# design.net
KiCad netlist of a schematic drawn in Altium Designer
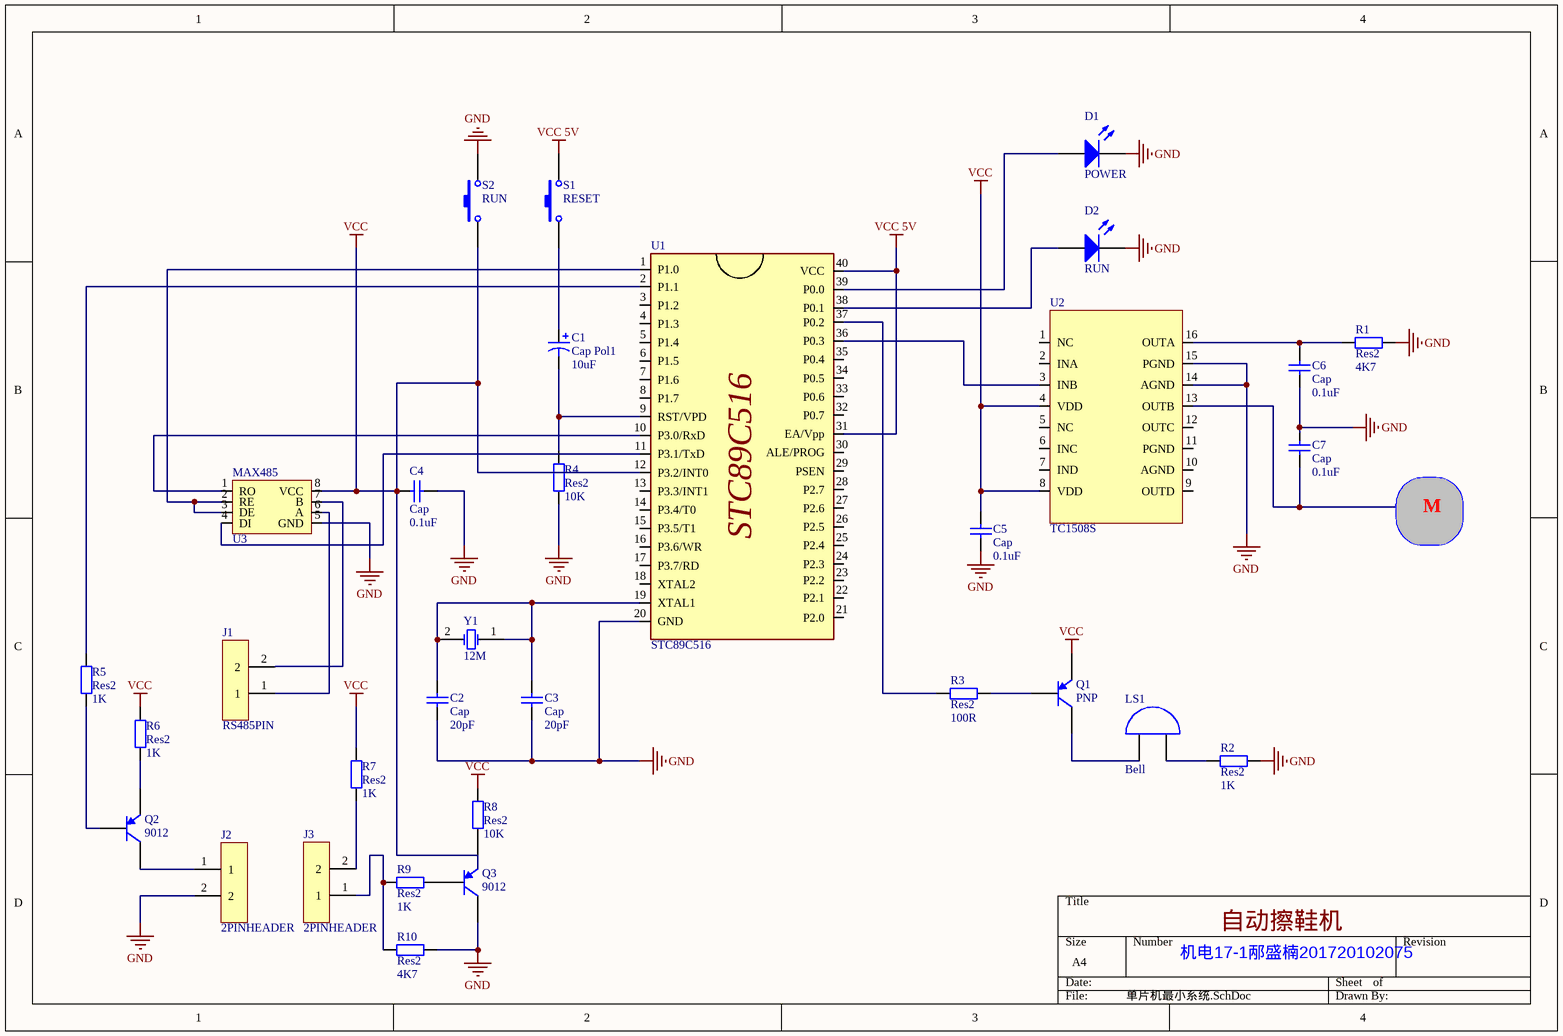
[diagram p0: 单片机最小系统.SchDoc]

(export (version "E")
  (design (tool "Eeschema 10.0.6"))
  (components
    (comp (ref "C1")
      (value "Cap Pol1")
      (footprint "RB7.6-15")
      (description "Polarized Capacitor (Radial)")
      (fields (field (name "ALTIUM_VALUE") "10uF") (field (name "PUBLISHER") "Altium Limited"))
      (libsource (lib "Miscellaneous Devices") (part "Cap Pol1"))
    )
    (comp (ref "C2")
      (value "Cap")
      (footprint "RAD-0.3")
      (description "Capacitor")
      (fields (field (name "ALTIUM_VALUE") "20pF") (field (name "PUBLISHER") "Altium Limited"))
      (libsource (lib "Miscellaneous Devices") (part "Cap"))
    )
    (comp (ref "C3")
      (value "Cap")
      (footprint "RAD-0.3")
      (description "Capacitor")
      (fields (field (name "ALTIUM_VALUE") "20pF") (field (name "PUBLISHER") "Altium Limited"))
      (libsource (lib "Miscellaneous Devices") (part "Cap"))
    )
    (comp (ref "C4")
      (value "Cap")
      (footprint "RAD-0.3")
      (description "Capacitor")
      (fields (field (name "ALTIUM_VALUE") "0.1uF") (field (name "PUBLISHER") "Altium Limited"))
      (libsource (lib "Miscellaneous Devices") (part "Cap"))
    )
    (comp (ref "C5")
      (value "Cap")
      (footprint "RAD-0.3")
      (description "Capacitor")
      (fields (field (name "ALTIUM_VALUE") "0.1uF") (field (name "PUBLISHER") "Altium Limited"))
      (libsource (lib "Miscellaneous Devices") (part "Cap"))
    )
    (comp (ref "C6")
      (value "Cap")
      (footprint "RAD-0.3")
      (description "Capacitor")
      (fields (field (name "ALTIUM_VALUE") "0.1uF") (field (name "PUBLISHER") "Altium Limited"))
      (libsource (lib "Miscellaneous Devices") (part "Cap"))
    )
    (comp (ref "C7")
      (value "Cap")
      (footprint "RAD-0.3")
      (description "Capacitor")
      (fields (field (name "ALTIUM_VALUE") "0.1uF") (field (name "PUBLISHER") "Altium Limited"))
      (libsource (lib "Miscellaneous Devices") (part "Cap"))
    )
    (comp (ref "D1")
      (value "POWER")
      (footprint "LED-0")
      (description "Typical INFRARED GaAs LED")
      (fields (field (name "PUBLISHER") "Altium Limited"))
      (libsource (lib "Miscellaneous Devices") (part "LED0"))
    )
    (comp (ref "D2")
      (value "RUN")
      (footprint "LED-0")
      (description "Typical INFRARED GaAs LED")
      (fields (field (name "PUBLISHER") "Altium Limited"))
      (libsource (lib "Miscellaneous Devices") (part "LED0"))
    )
    (comp (ref "J1") (value "RS485PIN") (libsource (lib "Schlib3") (part "Component_1")))
    (comp (ref "J2") (value "2PINHEADER") (libsource (lib "") (part "Component_1_1")))
    (comp (ref "J3") (value "2PINHEADER") (libsource (lib "Schlib3") (part "Component_1")))
    (comp (ref "LS1")
      (value "Bell")
      (footprint "PIN2")
      (description "Electrical Bell")
      (fields (field (name "PUBLISHER") "Altium Limited"))
      (libsource (lib "Miscellaneous Devices") (part "Bell"))
    )
    (comp (ref "MAX485") (value "U3") (footprint "MAX485") (libsource (lib "Schlib2") (part "Component_1")))
    (comp (ref "Q1")
      (value "PNP")
      (footprint "SOT-23B_N")
      (description "PNP Bipolar Transistor")
      (fields (field (name "PUBLISHER") "Altium Limited"))
      (libsource (lib "Miscellaneous Devices") (part "PNP"))
    )
    (comp (ref "Q2")
      (value "9012")
      (footprint "SOT-23B_N")
      (description "PNP Bipolar Transistor")
      (fields (field (name "PUBLISHER") "Altium Limited"))
      (libsource (lib "Miscellaneous Devices") (part "PNP"))
    )
    (comp (ref "Q3")
      (value "9012")
      (footprint "SOT-23B_L")
      (description "PNP Bipolar Transistor")
      (fields (field (name "PUBLISHER") "Altium Limited"))
      (libsource (lib "Miscellaneous Devices") (part "PNP"))
    )
    (comp (ref "R1")
      (value "Res2")
      (footprint "AXIAL-0.4")
      (description "Resistor")
      (fields (field (name "ALTIUM_VALUE") "4K7") (field (name "PUBLISHER") "Altium Limited"))
      (libsource (lib "") (part "Res2_1"))
    )
    (comp (ref "R2")
      (value "Res2")
      (footprint "AXIAL-0.4")
      (description "Resistor")
      (fields (field (name "ALTIUM_VALUE") "1K") (field (name "PUBLISHER") "Altium Limited"))
      (libsource (lib "") (part "Res2_1"))
    )
    (comp (ref "R3")
      (value "Res2")
      (footprint "AXIAL-0.4")
      (description "Resistor")
      (fields (field (name "ALTIUM_VALUE") "100R") (field (name "PUBLISHER") "Altium Limited"))
      (libsource (lib "") (part "Res2_1"))
    )
    (comp (ref "R4")
      (value "Res2")
      (footprint "AXIAL-0.4")
      (description "Resistor")
      (fields (field (name "ALTIUM_VALUE") "10K") (field (name "PUBLISHER") "Altium Limited"))
      (libsource (lib "Miscellaneous Devices") (part "Res2"))
    )
    (comp (ref "R5")
      (value "Res2")
      (footprint "AXIAL-0.4")
      (description "Resistor")
      (fields (field (name "ALTIUM_VALUE") "1K") (field (name "PUBLISHER") "Altium Limited"))
      (libsource (lib "Miscellaneous Devices") (part "Res2"))
    )
    (comp (ref "R6")
      (value "Res2")
      (footprint "AXIAL-0.4")
      (description "Resistor")
      (fields (field (name "ALTIUM_VALUE") "1K") (field (name "PUBLISHER") "Altium Limited"))
      (libsource (lib "Miscellaneous Devices") (part "Res2"))
    )
    (comp (ref "R7")
      (value "Res2")
      (footprint "AXIAL-0.4")
      (description "Resistor")
      (fields (field (name "ALTIUM_VALUE") "1K") (field (name "PUBLISHER") "Altium Limited"))
      (libsource (lib "Miscellaneous Devices") (part "Res2"))
    )
    (comp (ref "R8")
      (value "Res2")
      (footprint "AXIAL-0.4")
      (description "Resistor")
      (fields (field (name "ALTIUM_VALUE") "10K") (field (name "PUBLISHER") "Altium Limited"))
      (libsource (lib "Miscellaneous Devices") (part "Res2"))
    )
    (comp (ref "R9")
      (value "Res2")
      (footprint "AXIAL-0.4")
      (description "Resistor")
      (fields (field (name "ALTIUM_VALUE") "1K") (field (name "PUBLISHER") "Altium Limited"))
      (libsource (lib "") (part "Res2_1"))
    )
    (comp (ref "R10")
      (value "Res2")
      (footprint "AXIAL-0.4")
      (description "Resistor")
      (fields (field (name "ALTIUM_VALUE") "4K7") (field (name "PUBLISHER") "Altium Limited"))
      (libsource (lib "") (part "Res2_1"))
    )
    (comp (ref "S1")
      (value "RESET")
      (footprint "SPST-2")
      (description "Switch")
      (fields (field (name "PUBLISHER") "Altium Limited"))
      (libsource (lib "Miscellaneous Devices") (part "SW-PB"))
    )
    (comp (ref "S2")
      (value "RUN")
      (footprint "SPST-2")
      (description "Switch")
      (fields (field (name "PUBLISHER") "Altium Limited"))
      (libsource (lib "Miscellaneous Devices") (part "SW-PB"))
    )
    (comp (ref "U1")
      (value "STC89C516")
      (footprint "STC89C516")
      (libsource (lib "Schlib1") (part "STC89C516"))
    )
    (comp (ref "U2") (value "TC1508S") (footprint "TC1508S") (libsource (lib "TC1508S") (part "TC1508S")))
    (comp (ref "Y1")
      (value "12M")
      (footprint "R38")
      (description "Crystal Oscillator")
      (fields (field (name "PUBLISHER") "Altium Limited"))
      (libsource (lib "Miscellaneous Devices") (part "XTAL"))
    )
  )
  (nets
    (net (code "1") (name "GND") (class "Default")
      (node (ref "C2") (pin "1") (pinfunction "1_1") (pintype "passive"))
      (node (ref "C3") (pin "1") (pinfunction "1_1") (pintype "passive"))
      (node (ref "C4") (pin "2") (pinfunction "2_2") (pintype "passive"))
      (node (ref "C5") (pin "1") (pinfunction "1_1") (pintype "passive"))
      (node (ref "C6") (pin "1") (pinfunction "1_1") (pintype "passive"))
      (node (ref "C7") (pin "2") (pinfunction "2_2") (pintype "passive"))
      (node (ref "D1") (pin "2") (pinfunction "K_2") (pintype "passive"))
      (node (ref "D2") (pin "2") (pinfunction "K_2") (pintype "passive"))
      (node (ref "J2") (pin "2") (pinfunction "2_2") (pintype "passive"))
      (node (ref "MAX485") (pin "5") (pinfunction "GND_5") (pintype "passive"))
      (node (ref "Q3") (pin "1") (pinfunction "C_1") (pintype "passive"))
      (node (ref "R1") (pin "2") (pinfunction "2_2") (pintype "passive"))
      (node (ref "R10") (pin "2") (pinfunction "2_2") (pintype "passive"))
      (node (ref "R2") (pin "2") (pinfunction "2_2") (pintype "passive"))
      (node (ref "R4") (pin "1") (pinfunction "1_1") (pintype "passive"))
      (node (ref "S2") (pin "2") (pinfunction "2_2") (pintype "passive"))
      (node (ref "U1") (pin "20") (pinfunction "GND_20") (pintype "passive"))
      (node (ref "U2") (pin "14") (pinfunction "AGND_14") (pintype "passive"))
      (node (ref "U2") (pin "15") (pinfunction "PGND_15") (pintype "passive"))
    )
    (net (code "2") (name "Net-(C1-Pad1)") (class "Default")
      (node (ref "C1") (pin "1") (pinfunction "1_1") (pintype "passive"))
      (node (ref "S1") (pin "1") (pinfunction "1_1") (pintype "passive"))
    )
    (net (code "3") (name "Net-(D1-A)") (class "Default")
      (node (ref "D1") (pin "1") (pinfunction "A_1") (pintype "passive"))
      (node (ref "U1") (pin "39") (pinfunction "P0.0_39") (pintype "passive"))
    )
    (net (code "4") (name "Net-(D2-A)") (class "Default")
      (node (ref "D2") (pin "1") (pinfunction "A_1") (pintype "passive"))
      (node (ref "U1") (pin "38") (pinfunction "P0.1_38") (pintype "passive"))
    )
    (net (code "5") (name "Net-(J3-Pad1)") (class "Default")
      (node (ref "J3") (pin "1") (pinfunction "1_1") (pintype "passive"))
      (node (ref "R10") (pin "1") (pinfunction "1_1") (pintype "passive"))
      (node (ref "R9") (pin "1") (pinfunction "1_1") (pintype "passive"))
    )
    (net (code "6") (name "Net-(J3-Pad2)") (class "Default")
      (node (ref "J3") (pin "2") (pinfunction "2_2") (pintype "passive"))
      (node (ref "R7") (pin "1") (pinfunction "1_1") (pintype "passive"))
    )
    (net (code "7") (name "Net-(LS1-A)") (class "Default")
      (node (ref "LS1") (pin "1") (pinfunction "A_1") (pintype "passive"))
      (node (ref "Q1") (pin "1") (pinfunction "C_1") (pintype "passive"))
    )
    (net (code "8") (name "Net-(LS1-B)") (class "Default")
      (node (ref "LS1") (pin "2") (pinfunction "B_2") (pintype "passive"))
      (node (ref "R2") (pin "1") (pinfunction "1_1") (pintype "passive"))
    )
    (net (code "9") (name "Net-(MAX485-A)") (class "Default")
      (node (ref "J1") (pin "1") (pinfunction "1_1") (pintype "passive"))
      (node (ref "MAX485") (pin "6") (pinfunction "A_6") (pintype "passive"))
    )
    (net (code "10") (name "Net-(MAX485-B)") (class "Default")
      (node (ref "J1") (pin "2") (pinfunction "2_2") (pintype "passive"))
      (node (ref "MAX485") (pin "7") (pinfunction "B_7") (pintype "passive"))
    )
    (net (code "11") (name "Net-(MAX485-DE)") (class "Default")
      (node (ref "MAX485") (pin "2") (pinfunction "RE_2") (pintype "passive"))
      (node (ref "MAX485") (pin "3") (pinfunction "DE_3") (pintype "passive"))
      (node (ref "U1") (pin "1") (pinfunction "P1.0_1") (pintype "passive"))
    )
    (net (code "12") (name "Net-(MAX485-DI)") (class "Default")
      (node (ref "MAX485") (pin "4") (pinfunction "DI_4") (pintype "passive"))
      (node (ref "U1") (pin "11") (pinfunction "P3.1/TxD_11") (pintype "passive"))
    )
    (net (code "13") (name "Net-(MAX485-RO)") (class "Default")
      (node (ref "MAX485") (pin "1") (pinfunction "RO_1") (pintype "passive"))
      (node (ref "U1") (pin "10") (pinfunction "P3.0/RxD_10") (pintype "passive"))
    )
    (net (code "14") (name "Net-(Q1-B)") (class "Default")
      (node (ref "Q1") (pin "2") (pinfunction "B_2") (pintype "passive"))
      (node (ref "R3") (pin "2") (pinfunction "2_2") (pintype "passive"))
    )
    (net (code "15") (name "Net-(Q2-B)") (class "Default")
      (node (ref "Q2") (pin "2") (pinfunction "B_2") (pintype "passive"))
      (node (ref "R5") (pin "1") (pinfunction "1_1") (pintype "passive"))
    )
    (net (code "16") (name "Net-(Q2-C)") (class "Default")
      (node (ref "J2") (pin "1") (pinfunction "1_1") (pintype "passive"))
      (node (ref "Q2") (pin "1") (pinfunction "C_1") (pintype "passive"))
    )
    (net (code "17") (name "Net-(Q2-E)") (class "Default")
      (node (ref "Q2") (pin "3") (pinfunction "E_3") (pintype "passive"))
      (node (ref "R6") (pin "1") (pinfunction "1_1") (pintype "passive"))
    )
    (net (code "18") (name "Net-(Q3-B)") (class "Default")
      (node (ref "Q3") (pin "2") (pinfunction "B_2") (pintype "passive"))
      (node (ref "R9") (pin "2") (pinfunction "2_2") (pintype "passive"))
    )
    (net (code "19") (name "Net-(Q3-E)") (class "Default")
      (node (ref "Q3") (pin "3") (pinfunction "E_3") (pintype "passive"))
      (node (ref "R8") (pin "1") (pinfunction "1_1") (pintype "passive"))
    )
    (net (code "20") (name "Net-(U1-P0.2)") (class "Default")
      (node (ref "R3") (pin "1") (pinfunction "1_1") (pintype "passive"))
      (node (ref "U1") (pin "37") (pinfunction "P0.2_37") (pintype "passive"))
    )
    (net (code "21") (name "Net-(U1-P0.3)") (class "Default")
      (node (ref "U1") (pin "36") (pinfunction "P0.3_36") (pintype "passive"))
      (node (ref "U2") (pin "3") (pinfunction "INB_3") (pintype "passive"))
    )
    (net (code "22") (name "Net-(U1-P1.1)") (class "Default")
      (node (ref "R5") (pin "2") (pinfunction "2_2") (pintype "passive"))
      (node (ref "U1") (pin "2") (pinfunction "P1.1_2") (pintype "passive"))
    )
    (net (code "23") (name "Net-(U1-RST{slash}VPD)") (class "Default")
      (node (ref "C1") (pin "2") (pinfunction "2_2") (pintype "passive"))
      (node (ref "R4") (pin "2") (pinfunction "2_2") (pintype "passive"))
      (node (ref "U1") (pin "9") (pinfunction "RST/VPD_9") (pintype "passive"))
    )
    (net (code "24") (name "Net-(U1-XTAL1)") (class "Default")
      (node (ref "C2") (pin "2") (pinfunction "2_2") (pintype "passive"))
      (node (ref "C3") (pin "2") (pinfunction "2_2") (pintype "passive"))
      (node (ref "U1") (pin "19") (pinfunction "XTAL1_19") (pintype "passive"))
      (node (ref "Y1") (pin "1") (pinfunction "OSC1_1") (pintype "passive"))
      (node (ref "Y1") (pin "2") (pinfunction "OSC2_2") (pintype "passive"))
    )
    (net (code "25") (name "Net-(U2-OUTA)") (class "Default")
      (node (ref "C6") (pin "2") (pinfunction "2_2") (pintype "passive"))
      (node (ref "R1") (pin "1") (pinfunction "1_1") (pintype "passive"))
      (node (ref "U2") (pin "16") (pinfunction "OUTA_16") (pintype "passive"))
    )
    (net (code "26") (name "Net-(U2-OUTB)") (class "Default")
      (node (ref "C7") (pin "1") (pinfunction "1_1") (pintype "passive"))
      (node (ref "U2") (pin "13") (pinfunction "OUTB_13") (pintype "passive"))
    )
    (net (code "27") (name "VCC") (class "Default")
      (node (ref "C4") (pin "1") (pinfunction "1_1") (pintype "passive"))
      (node (ref "C5") (pin "2") (pinfunction "2_2") (pintype "passive"))
      (node (ref "MAX485") (pin "8") (pinfunction "VCC_8") (pintype "passive"))
      (node (ref "Q1") (pin "3") (pinfunction "E_3") (pintype "passive"))
      (node (ref "R6") (pin "2") (pinfunction "2_2") (pintype "passive"))
      (node (ref "R7") (pin "2") (pinfunction "2_2") (pintype "passive"))
      (node (ref "R8") (pin "2") (pinfunction "2_2") (pintype "passive"))
      (node (ref "S2") (pin "1") (pinfunction "1_1") (pintype "passive"))
      (node (ref "U1") (pin "12") (pinfunction "P3.2/INT0_12") (pintype "passive"))
      (node (ref "U2") (pin "4") (pinfunction "VDD_4") (pintype "passive"))
      (node (ref "U2") (pin "8") (pinfunction "VDD_8") (pintype "passive"))
    )
    (net (code "28") (name "VCC 5V") (class "Default")
      (node (ref "S1") (pin "2") (pinfunction "2_2") (pintype "passive"))
      (node (ref "U1") (pin "31") (pinfunction "EA/Vpp_31") (pintype "passive"))
      (node (ref "U1") (pin "40") (pinfunction "VCC_40") (pintype "passive"))
    )
    (net (code "29") (name "unconnected-(U1-ALE{slash}PROG-Pad30)") (class "Default")
      (node (ref "U1") (pin "30") (pinfunction "ALE/PROG_30") (pintype "passive"))
    )
    (net (code "30") (name "unconnected-(U1-P0.4-Pad35)") (class "Default")
      (node (ref "U1") (pin "35") (pinfunction "P0.4_35") (pintype "passive"))
    )
    (net (code "31") (name "unconnected-(U1-P0.5-Pad34)") (class "Default")
      (node (ref "U1") (pin "34") (pinfunction "P0.5_34") (pintype "passive"))
    )
    (net (code "32") (name "unconnected-(U1-P0.6-Pad33)") (class "Default")
      (node (ref "U1") (pin "33") (pinfunction "P0.6_33") (pintype "passive"))
    )
    (net (code "33") (name "unconnected-(U1-P0.7-Pad32)") (class "Default")
      (node (ref "U1") (pin "32") (pinfunction "P0.7_32") (pintype "passive"))
    )
    (net (code "34") (name "unconnected-(U1-P1.2-Pad3)") (class "Default")
      (node (ref "U1") (pin "3") (pinfunction "P1.2_3") (pintype "passive"))
    )
    (net (code "35") (name "unconnected-(U1-P1.3-Pad4)") (class "Default")
      (node (ref "U1") (pin "4") (pinfunction "P1.3_4") (pintype "passive"))
    )
    (net (code "36") (name "unconnected-(U1-P1.4-Pad5)") (class "Default")
      (node (ref "U1") (pin "5") (pinfunction "P1.4_5") (pintype "passive"))
    )
    (net (code "37") (name "unconnected-(U1-P1.5-Pad6)") (class "Default")
      (node (ref "U1") (pin "6") (pinfunction "P1.5_6") (pintype "passive"))
    )
    (net (code "38") (name "unconnected-(U1-P1.6-Pad7)") (class "Default")
      (node (ref "U1") (pin "7") (pinfunction "P1.6_7") (pintype "passive"))
    )
    (net (code "39") (name "unconnected-(U1-P1.7-Pad8)") (class "Default")
      (node (ref "U1") (pin "8") (pinfunction "P1.7_8") (pintype "passive"))
    )
    (net (code "40") (name "unconnected-(U1-P2.0-Pad21)") (class "Default")
      (node (ref "U1") (pin "21") (pinfunction "P2.0_21") (pintype "passive"))
    )
    (net (code "41") (name "unconnected-(U1-P2.1-Pad22)") (class "Default")
      (node (ref "U1") (pin "22") (pinfunction "P2.1_22") (pintype "passive"))
    )
    (net (code "42") (name "unconnected-(U1-P2.2-Pad23)") (class "Default")
      (node (ref "U1") (pin "23") (pinfunction "P2.2_23") (pintype "passive"))
    )
    (net (code "43") (name "unconnected-(U1-P2.3-Pad24)") (class "Default")
      (node (ref "U1") (pin "24") (pinfunction "P2.3_24") (pintype "passive"))
    )
    (net (code "44") (name "unconnected-(U1-P2.4-Pad25)") (class "Default")
      (node (ref "U1") (pin "25") (pinfunction "P2.4_25") (pintype "passive"))
    )
    (net (code "45") (name "unconnected-(U1-P2.5-Pad26)") (class "Default")
      (node (ref "U1") (pin "26") (pinfunction "P2.5_26") (pintype "passive"))
    )
    (net (code "46") (name "unconnected-(U1-P2.6-Pad27)") (class "Default")
      (node (ref "U1") (pin "27") (pinfunction "P2.6_27") (pintype "passive"))
    )
    (net (code "47") (name "unconnected-(U1-P2.7-Pad28)") (class "Default")
      (node (ref "U1") (pin "28") (pinfunction "P2.7_28") (pintype "passive"))
    )
    (net (code "48") (name "unconnected-(U1-P3.3{slash}INT1-Pad13)") (class "Default")
      (node (ref "U1") (pin "13") (pinfunction "P3.3/INT1_13") (pintype "passive"))
    )
    (net (code "49") (name "unconnected-(U1-P3.4{slash}T0-Pad14)") (class "Default")
      (node (ref "U1") (pin "14") (pinfunction "P3.4/T0_14") (pintype "passive"))
    )
    (net (code "50") (name "unconnected-(U1-P3.5{slash}T1-Pad15)") (class "Default")
      (node (ref "U1") (pin "15") (pinfunction "P3.5/T1_15") (pintype "passive"))
    )
    (net (code "51") (name "unconnected-(U1-P3.6{slash}WR-Pad16)") (class "Default")
      (node (ref "U1") (pin "16") (pinfunction "P3.6/WR_16") (pintype "passive"))
    )
    (net (code "52") (name "unconnected-(U1-P3.7{slash}RD-Pad17)") (class "Default")
      (node (ref "U1") (pin "17") (pinfunction "P3.7/RD_17") (pintype "passive"))
    )
    (net (code "53") (name "unconnected-(U1-PSEN-Pad29)") (class "Default")
      (node (ref "U1") (pin "29") (pinfunction "PSEN_29") (pintype "passive"))
    )
    (net (code "54") (name "unconnected-(U1-XTAL2-Pad18)") (class "Default")
      (node (ref "U1") (pin "18") (pinfunction "XTAL2_18") (pintype "passive"))
    )
    (net (code "55") (name "unconnected-(U2-AGND-Pad10)") (class "Default")
      (node (ref "U2") (pin "10") (pinfunction "AGND_10") (pintype "passive"))
    )
    (net (code "56") (name "unconnected-(U2-INA-Pad2)") (class "Default")
      (node (ref "U2") (pin "2") (pinfunction "INA_2") (pintype "passive"))
    )
    (net (code "57") (name "unconnected-(U2-INC-Pad6)") (class "Default")
      (node (ref "U2") (pin "6") (pinfunction "INC_6") (pintype "passive"))
    )
    (net (code "58") (name "unconnected-(U2-IND-Pad7)") (class "Default")
      (node (ref "U2") (pin "7") (pinfunction "IND_7") (pintype "passive"))
    )
    (net (code "59") (name "unconnected-(U2-NC-Pad1)") (class "Default")
      (node (ref "U2") (pin "1") (pinfunction "NC_1") (pintype "passive"))
    )
    (net (code "60") (name "unconnected-(U2-NC-Pad5)") (class "Default")
      (node (ref "U2") (pin "5") (pinfunction "NC_5") (pintype "passive"))
    )
    (net (code "61") (name "unconnected-(U2-OUTC-Pad12)") (class "Default")
      (node (ref "U2") (pin "12") (pinfunction "OUTC_12") (pintype "passive"))
    )
    (net (code "62") (name "unconnected-(U2-OUTD-Pad9)") (class "Default")
      (node (ref "U2") (pin "9") (pinfunction "OUTD_9") (pintype "passive"))
    )
    (net (code "63") (name "unconnected-(U2-PGND-Pad11)") (class "Default")
      (node (ref "U2") (pin "11") (pinfunction "PGND_11") (pintype "passive"))
    )
  )
)
